# BX31_IoT_Board.net
KiCad netlist of a schematic drawn in EAGLE
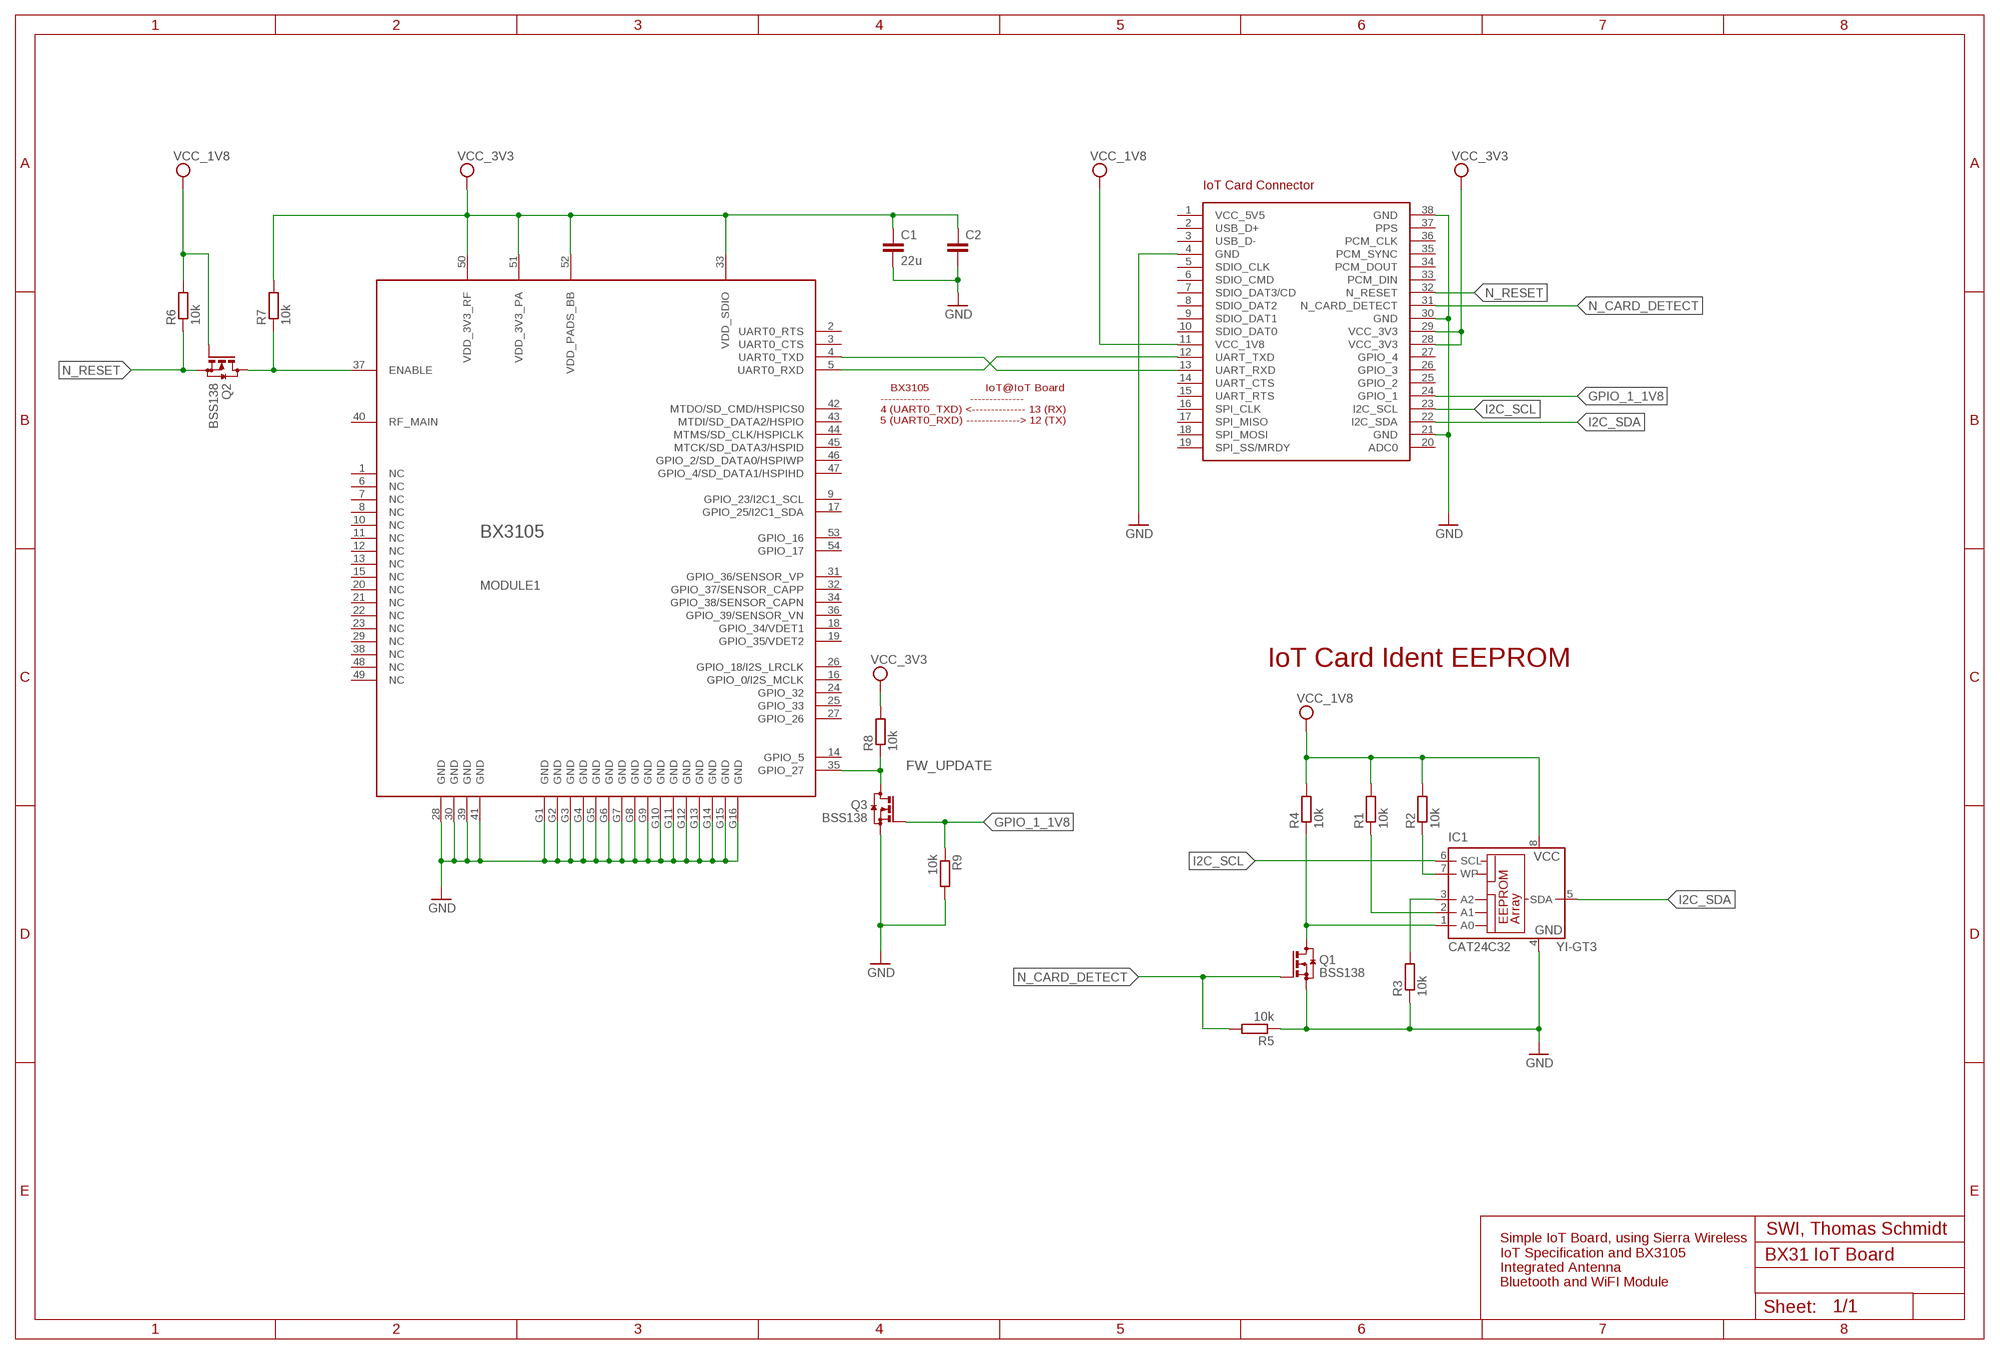
[diagram p0: schematic, sheet 1]

(export (version "E")
  (design (tool "Eeschema 10.0.6"))
  (components
    (comp (ref "C1")
      (value "22u")
      (footprint "eagle-import:C0805K")
      (libsource (lib "eagle-import") (part "C-EUC0805K"))
    )
    (comp (ref "C2")
      (value "C-EUC0603K")
      (footprint "eagle-import:C0603K")
      (libsource (lib "eagle-import") (part "C-EUC0603K"))
    )
    (comp (ref "IC1")
      (value "CAT24C32 YI-GT3")
      (footprint "eagle-import:TSSOP8")
      (fields (field (name "MPN") "CAT24C64YI-GT3"))
      (libsource (lib "eagle-import") (part "24STC64"))
    )
    (comp (ref "MODULE1")
      (value "BX3105")
      (footprint "eagle-import:BX3105")
      (libsource (lib "eagle-import") (part "BX3105"))
    )
    (comp (ref "Q1")
      (value "BSS138")
      (footprint "eagle-import:SOT23")
      (libsource (lib "eagle-import") (part "BSS123"))
    )
    (comp (ref "Q2")
      (value "BSS138")
      (footprint "eagle-import:SOT23")
      (libsource (lib "eagle-import") (part "BSS123"))
    )
    (comp (ref "Q3")
      (value "BSS138")
      (footprint "eagle-import:SOT23")
      (libsource (lib "eagle-import") (part "BSS123"))
    )
    (comp (ref "R1")
      (value "10k")
      (footprint "eagle-import:R0402")
      (libsource (lib "eagle-import") (part "R-EU_R0402"))
    )
    (comp (ref "R2")
      (value "10k")
      (footprint "eagle-import:R0402")
      (libsource (lib "eagle-import") (part "R-EU_R0402"))
    )
    (comp (ref "R3")
      (value "10k")
      (footprint "eagle-import:R0402")
      (libsource (lib "eagle-import") (part "R-EU_R0402"))
    )
    (comp (ref "R4")
      (value "10k")
      (footprint "eagle-import:R0402")
      (libsource (lib "eagle-import") (part "R-EU_R0402"))
    )
    (comp (ref "R5")
      (value "10k")
      (footprint "eagle-import:R0402")
      (libsource (lib "eagle-import") (part "R-EU_R0402"))
    )
    (comp (ref "R6")
      (value "10k")
      (footprint "eagle-import:R0402")
      (libsource (lib "eagle-import") (part "R-EU_R0402"))
    )
    (comp (ref "R7")
      (value "10k")
      (footprint "eagle-import:R0402")
      (libsource (lib "eagle-import") (part "R-EU_R0402"))
    )
    (comp (ref "R8")
      (value "10k")
      (footprint "eagle-import:R0402")
      (libsource (lib "eagle-import") (part "R-EU_R0402"))
    )
    (comp (ref "R9")
      (value "10k")
      (footprint "eagle-import:R0402")
      (libsource (lib "eagle-import") (part "R-EU_R0402"))
    )
    (comp (ref "U$1")
      (value "IOT")
      (footprint "eagle-import:IOT")
      (libsource (lib "eagle-import") (part "IOT"))
    )
  )
  (nets
    (net (code "1") (name "/FW_UPDATE") (class "Default")
      (node (ref "MODULE1") (pin "35") (pinfunction "GPIO_27_35") (pintype "bidirectional"))
      (node (ref "Q3") (pin "3") (pinfunction "D_3") (pintype "passive"))
      (node (ref "R8") (pin "1") (pinfunction "1_1") (pintype "passive"))
    )
    (net (code "2") (name "/VCC_5V5") (class "Default")
      (node (ref "U$1") (pin "1") (pinfunction "VCC_5V5_1") (pintype "power_in"))
    )
    (net (code "3") (name "GND") (class "Default")
      (node (ref "C1") (pin "2") (pinfunction "2_2") (pintype "passive"))
      (node (ref "C2") (pin "2") (pinfunction "2_2") (pintype "passive"))
      (node (ref "IC1") (pin "4") (pinfunction "GND_4") (pintype "power_in"))
      (node (ref "MODULE1") (pin "28") (pinfunction "GND_28") (pintype "power_in"))
      (node (ref "MODULE1") (pin "30") (pinfunction "GND_30") (pintype "power_in"))
      (node (ref "MODULE1") (pin "39") (pinfunction "GND_39") (pintype "power_in"))
      (node (ref "MODULE1") (pin "41") (pinfunction "GND_41") (pintype "power_in"))
      (node (ref "MODULE1") (pin "G1") (pinfunction "GND_G1") (pintype "power_in"))
      (node (ref "MODULE1") (pin "G10") (pinfunction "GND_G10") (pintype "power_in"))
      (node (ref "MODULE1") (pin "G11") (pinfunction "GND_G11") (pintype "power_in"))
      (node (ref "MODULE1") (pin "G12") (pinfunction "GND_G12") (pintype "power_in"))
      (node (ref "MODULE1") (pin "G13") (pinfunction "GND_G13") (pintype "power_in"))
      (node (ref "MODULE1") (pin "G14") (pinfunction "GND_G14") (pintype "power_in"))
      (node (ref "MODULE1") (pin "G15") (pinfunction "GND_G15") (pintype "power_in"))
      (node (ref "MODULE1") (pin "G16") (pinfunction "GND_G16") (pintype "power_in"))
      (node (ref "MODULE1") (pin "G2") (pinfunction "GND_G2") (pintype "power_in"))
      (node (ref "MODULE1") (pin "G3") (pinfunction "GND_G3") (pintype "power_in"))
      (node (ref "MODULE1") (pin "G4") (pinfunction "GND_G4") (pintype "power_in"))
      (node (ref "MODULE1") (pin "G5") (pinfunction "GND_G5") (pintype "power_in"))
      (node (ref "MODULE1") (pin "G6") (pinfunction "GND_G6") (pintype "power_in"))
      (node (ref "MODULE1") (pin "G7") (pinfunction "GND_G7") (pintype "power_in"))
      (node (ref "MODULE1") (pin "G8") (pinfunction "GND_G8") (pintype "power_in"))
      (node (ref "MODULE1") (pin "G9") (pinfunction "GND_G9") (pintype "power_in"))
      (node (ref "Q1") (pin "2") (pinfunction "S_2") (pintype "passive"))
      (node (ref "Q3") (pin "2") (pinfunction "S_2") (pintype "passive"))
      (node (ref "R3") (pin "1") (pinfunction "1_1") (pintype "passive"))
      (node (ref "R5") (pin "1") (pinfunction "1_1") (pintype "passive"))
      (node (ref "R9") (pin "2") (pinfunction "2_2") (pintype "passive"))
      (node (ref "U$1") (pin "21") (pinfunction "GND_21") (pintype "power_in"))
      (node (ref "U$1") (pin "30") (pinfunction "GND_30") (pintype "power_in"))
      (node (ref "U$1") (pin "38") (pinfunction "GND_38") (pintype "bidirectional"))
      (node (ref "U$1") (pin "4") (pinfunction "GND_4") (pintype "power_in"))
    )
    (net (code "4") (name "GPIO_1_1V8") (class "Default")
      (node (ref "Q3") (pin "1") (pinfunction "G_1") (pintype "passive"))
      (node (ref "R9") (pin "1") (pinfunction "1_1") (pintype "passive"))
      (node (ref "U$1") (pin "24") (pinfunction "GPIO_1_24") (pintype "bidirectional"))
    )
    (net (code "5") (name "I2C_SCL") (class "Default")
      (node (ref "IC1") (pin "6") (pinfunction "SCL_6") (pintype "input"))
      (node (ref "U$1") (pin "23") (pinfunction "I2C_SCL_23") (pintype "input"))
    )
    (net (code "6") (name "I2C_SDA") (class "Default")
      (node (ref "IC1") (pin "5") (pinfunction "SDA_5") (pintype "bidirectional"))
      (node (ref "U$1") (pin "22") (pinfunction "I2C_SDA_22") (pintype "bidirectional"))
    )
    (net (code "7") (name "N_CARD_DETECT") (class "Default")
      (node (ref "Q1") (pin "1") (pinfunction "G_1") (pintype "passive"))
      (node (ref "R5") (pin "2") (pinfunction "2_2") (pintype "passive"))
      (node (ref "U$1") (pin "31") (pinfunction "N_CARD_DETECT_31") (pintype "bidirectional"))
    )
    (net (code "8") (name "N_RESET") (class "Default")
      (node (ref "Q2") (pin "2") (pinfunction "S_2") (pintype "passive"))
      (node (ref "R6") (pin "1") (pinfunction "1_1") (pintype "passive"))
      (node (ref "U$1") (pin "32") (pinfunction "N_RESET_32") (pintype "bidirectional"))
    )
    (net (code "9") (name "Net-(IC1-A0)") (class "Default")
      (node (ref "IC1") (pin "1") (pinfunction "A0_1") (pintype "input"))
      (node (ref "Q1") (pin "3") (pinfunction "D_3") (pintype "passive"))
      (node (ref "R4") (pin "1") (pinfunction "1_1") (pintype "passive"))
    )
    (net (code "10") (name "Net-(IC1-A1)") (class "Default")
      (node (ref "IC1") (pin "2") (pinfunction "A1_2") (pintype "input"))
      (node (ref "R1") (pin "1") (pinfunction "1_1") (pintype "passive"))
    )
    (net (code "11") (name "Net-(IC1-A2)") (class "Default")
      (node (ref "IC1") (pin "3") (pinfunction "A2_3") (pintype "input"))
      (node (ref "R3") (pin "2") (pinfunction "2_2") (pintype "passive"))
    )
    (net (code "12") (name "Net-(IC1-WP)") (class "Default")
      (node (ref "IC1") (pin "7") (pinfunction "WP_7") (pintype "input"))
      (node (ref "R2") (pin "1") (pinfunction "1_1") (pintype "passive"))
    )
    (net (code "13") (name "Net-(MODULE1-ENABLE)") (class "Default")
      (node (ref "MODULE1") (pin "37") (pinfunction "ENABLE_37") (pintype "input"))
      (node (ref "Q2") (pin "3") (pinfunction "D_3") (pintype "passive"))
      (node (ref "R7") (pin "1") (pinfunction "1_1") (pintype "passive"))
    )
    (net (code "14") (name "Net-(MODULE1-UART0_RXD)") (class "Default")
      (node (ref "MODULE1") (pin "5") (pinfunction "UART0_RXD_5") (pintype "output"))
      (node (ref "U$1") (pin "12") (pinfunction "UART_TXD_12") (pintype "output"))
    )
    (net (code "15") (name "Net-(MODULE1-UART0_TXD)") (class "Default")
      (node (ref "MODULE1") (pin "4") (pinfunction "UART0_TXD_4") (pintype "input"))
      (node (ref "U$1") (pin "13") (pinfunction "UART_RXD_13") (pintype "input"))
    )
    (net (code "16") (name "VCC_1V8") (class "Default")
      (node (ref "IC1") (pin "8") (pinfunction "VCC_8") (pintype "power_in"))
      (node (ref "Q2") (pin "1") (pinfunction "G_1") (pintype "passive"))
      (node (ref "R1") (pin "2") (pinfunction "2_2") (pintype "passive"))
      (node (ref "R2") (pin "2") (pinfunction "2_2") (pintype "passive"))
      (node (ref "R4") (pin "2") (pinfunction "2_2") (pintype "passive"))
      (node (ref "R6") (pin "2") (pinfunction "2_2") (pintype "passive"))
      (node (ref "U$1") (pin "11") (pinfunction "VCC_1V8_11") (pintype "power_in"))
    )
    (net (code "17") (name "VCC_3V3") (class "Default")
      (node (ref "C1") (pin "1") (pinfunction "1_1") (pintype "passive"))
      (node (ref "C2") (pin "1") (pinfunction "1_1") (pintype "passive"))
      (node (ref "MODULE1") (pin "33") (pinfunction "VDD_SDIO_33") (pintype "power_in"))
      (node (ref "MODULE1") (pin "50") (pinfunction "VDD_3V3_RF_50") (pintype "power_in"))
      (node (ref "MODULE1") (pin "51") (pinfunction "VDD_3V3_PA_51") (pintype "power_in"))
      (node (ref "MODULE1") (pin "52") (pinfunction "VDD_PADS_BB_52") (pintype "power_in"))
      (node (ref "R7") (pin "2") (pinfunction "2_2") (pintype "passive"))
      (node (ref "R8") (pin "2") (pinfunction "2_2") (pintype "passive"))
      (node (ref "U$1") (pin "28") (pinfunction "VCC_3V3_28") (pintype "power_in"))
      (node (ref "U$1") (pin "29") (pinfunction "VCC_3V3_29") (pintype "power_in"))
    )
    (net (code "18") (name "unconnected-(MODULE1-GPIO_0{slash}I2S_MCLK-Pad16)") (class "Default")
      (node (ref "MODULE1") (pin "16") (pinfunction "GPIO_0/I2S_MCLK_16") (pintype "bidirectional"))
    )
    (net (code "19") (name "unconnected-(MODULE1-GPIO_2{slash}SD_DATA0{slash}HSPIWP-Pad46)") (class "Default")
      (node (ref "MODULE1") (pin "46") (pinfunction "GPIO_2/SD_DATA0/HSPIWP_46") (pintype "bidirectional"))
    )
    (net (code "20") (name "unconnected-(MODULE1-GPIO_4{slash}SD_DATA1{slash}HSPIHD-Pad47)") (class "Default")
      (node (ref "MODULE1") (pin "47") (pinfunction "GPIO_4/SD_DATA1/HSPIHD_47") (pintype "bidirectional"))
    )
    (net (code "21") (name "unconnected-(MODULE1-GPIO_5-Pad14)") (class "Default")
      (node (ref "MODULE1") (pin "14") (pinfunction "GPIO_5_14") (pintype "bidirectional"))
    )
    (net (code "22") (name "unconnected-(MODULE1-GPIO_16-Pad53)") (class "Default")
      (node (ref "MODULE1") (pin "53") (pinfunction "GPIO_16_53") (pintype "bidirectional"))
    )
    (net (code "23") (name "unconnected-(MODULE1-GPIO_17-Pad54)") (class "Default")
      (node (ref "MODULE1") (pin "54") (pinfunction "GPIO_17_54") (pintype "bidirectional"))
    )
    (net (code "24") (name "unconnected-(MODULE1-GPIO_18{slash}I2S_LRCLK-Pad26)") (class "Default")
      (node (ref "MODULE1") (pin "26") (pinfunction "GPIO_18/I2S_LRCLK_26") (pintype "bidirectional"))
    )
    (net (code "25") (name "unconnected-(MODULE1-GPIO_23{slash}I2C1_SCL-Pad9)") (class "Default")
      (node (ref "MODULE1") (pin "9") (pinfunction "GPIO_23/I2C1_SCL_9") (pintype "bidirectional"))
    )
    (net (code "26") (name "unconnected-(MODULE1-GPIO_25{slash}I2C1_SDA-Pad17)") (class "Default")
      (node (ref "MODULE1") (pin "17") (pinfunction "GPIO_25/I2C1_SDA_17") (pintype "bidirectional"))
    )
    (net (code "27") (name "unconnected-(MODULE1-GPIO_26-Pad27)") (class "Default")
      (node (ref "MODULE1") (pin "27") (pinfunction "GPIO_26_27") (pintype "bidirectional"))
    )
    (net (code "28") (name "unconnected-(MODULE1-GPIO_32-Pad24)") (class "Default")
      (node (ref "MODULE1") (pin "24") (pinfunction "GPIO_32_24") (pintype "bidirectional"))
    )
    (net (code "29") (name "unconnected-(MODULE1-GPIO_33-Pad25)") (class "Default")
      (node (ref "MODULE1") (pin "25") (pinfunction "GPIO_33_25") (pintype "bidirectional"))
    )
    (net (code "30") (name "unconnected-(MODULE1-GPIO_34{slash}VDET1-Pad18)") (class "Default")
      (node (ref "MODULE1") (pin "18") (pinfunction "GPIO_34/VDET1_18") (pintype "bidirectional"))
    )
    (net (code "31") (name "unconnected-(MODULE1-GPIO_35{slash}VDET2-Pad19)") (class "Default")
      (node (ref "MODULE1") (pin "19") (pinfunction "GPIO_35/VDET2_19") (pintype "bidirectional"))
    )
    (net (code "32") (name "unconnected-(MODULE1-GPIO_36{slash}SENSOR_VP-Pad31)") (class "Default")
      (node (ref "MODULE1") (pin "31") (pinfunction "GPIO_36/SENSOR_VP_31") (pintype "bidirectional"))
    )
    (net (code "33") (name "unconnected-(MODULE1-GPIO_37{slash}SENSOR_CAPP-Pad32)") (class "Default")
      (node (ref "MODULE1") (pin "32") (pinfunction "GPIO_37/SENSOR_CAPP_32") (pintype "bidirectional"))
    )
    (net (code "34") (name "unconnected-(MODULE1-GPIO_38{slash}SENSOR_CAPN-Pad34)") (class "Default")
      (node (ref "MODULE1") (pin "34") (pinfunction "GPIO_38/SENSOR_CAPN_34") (pintype "bidirectional"))
    )
    (net (code "35") (name "unconnected-(MODULE1-GPIO_39{slash}SENSOR_VN-Pad36)") (class "Default")
      (node (ref "MODULE1") (pin "36") (pinfunction "GPIO_39/SENSOR_VN_36") (pintype "bidirectional"))
    )
    (net (code "36") (name "unconnected-(MODULE1-MTCK{slash}SD_DATA3{slash}HSPID-Pad45)") (class "Default")
      (node (ref "MODULE1") (pin "45") (pinfunction "MTCK/SD_DATA3/HSPID_45") (pintype "bidirectional"))
    )
    (net (code "37") (name "unconnected-(MODULE1-MTDI{slash}SD_DATA2{slash}HSPIO-Pad43)") (class "Default")
      (node (ref "MODULE1") (pin "43") (pinfunction "MTDI/SD_DATA2/HSPIO_43") (pintype "bidirectional"))
    )
    (net (code "38") (name "unconnected-(MODULE1-MTDO{slash}SD_CMD{slash}HSPICS0-Pad42)") (class "Default")
      (node (ref "MODULE1") (pin "42") (pinfunction "MTDO/SD_CMD/HSPICS0_42") (pintype "bidirectional"))
    )
    (net (code "39") (name "unconnected-(MODULE1-MTMS{slash}SD_CLK{slash}HSPICLK-Pad44)") (class "Default")
      (node (ref "MODULE1") (pin "44") (pinfunction "MTMS/SD_CLK/HSPICLK_44") (pintype "bidirectional"))
    )
    (net (code "40") (name "unconnected-(MODULE1-NC-Pad1)") (class "Default")
      (node (ref "MODULE1") (pin "1") (pinfunction "NC_1") (pintype "no_connect"))
    )
    (net (code "41") (name "unconnected-(MODULE1-NC-Pad6)") (class "Default")
      (node (ref "MODULE1") (pin "6") (pinfunction "NC_6") (pintype "no_connect"))
    )
    (net (code "42") (name "unconnected-(MODULE1-NC-Pad7)") (class "Default")
      (node (ref "MODULE1") (pin "7") (pinfunction "NC_7") (pintype "no_connect"))
    )
    (net (code "43") (name "unconnected-(MODULE1-NC-Pad8)") (class "Default")
      (node (ref "MODULE1") (pin "8") (pinfunction "NC_8") (pintype "no_connect"))
    )
    (net (code "44") (name "unconnected-(MODULE1-NC-Pad10)") (class "Default")
      (node (ref "MODULE1") (pin "10") (pinfunction "NC_10") (pintype "no_connect"))
    )
    (net (code "45") (name "unconnected-(MODULE1-NC-Pad11)") (class "Default")
      (node (ref "MODULE1") (pin "11") (pinfunction "NC_11") (pintype "no_connect"))
    )
    (net (code "46") (name "unconnected-(MODULE1-NC-Pad12)") (class "Default")
      (node (ref "MODULE1") (pin "12") (pinfunction "NC_12") (pintype "no_connect"))
    )
    (net (code "47") (name "unconnected-(MODULE1-NC-Pad13)") (class "Default")
      (node (ref "MODULE1") (pin "13") (pinfunction "NC_13") (pintype "no_connect"))
    )
    (net (code "48") (name "unconnected-(MODULE1-NC-Pad15)") (class "Default")
      (node (ref "MODULE1") (pin "15") (pinfunction "NC_15") (pintype "no_connect"))
    )
    (net (code "49") (name "unconnected-(MODULE1-NC-Pad20)") (class "Default")
      (node (ref "MODULE1") (pin "20") (pinfunction "NC_20") (pintype "no_connect"))
    )
    (net (code "50") (name "unconnected-(MODULE1-NC-Pad21)") (class "Default")
      (node (ref "MODULE1") (pin "21") (pinfunction "NC_21") (pintype "no_connect"))
    )
    (net (code "51") (name "unconnected-(MODULE1-NC-Pad22)") (class "Default")
      (node (ref "MODULE1") (pin "22") (pinfunction "NC_22") (pintype "no_connect"))
    )
    (net (code "52") (name "unconnected-(MODULE1-NC-Pad23)") (class "Default")
      (node (ref "MODULE1") (pin "23") (pinfunction "NC_23") (pintype "no_connect"))
    )
    (net (code "53") (name "unconnected-(MODULE1-NC-Pad29)") (class "Default")
      (node (ref "MODULE1") (pin "29") (pinfunction "NC_29") (pintype "no_connect"))
    )
    (net (code "54") (name "unconnected-(MODULE1-NC-Pad38)") (class "Default")
      (node (ref "MODULE1") (pin "38") (pinfunction "NC_38") (pintype "no_connect"))
    )
    (net (code "55") (name "unconnected-(MODULE1-NC-Pad48)") (class "Default")
      (node (ref "MODULE1") (pin "48") (pinfunction "NC_48") (pintype "no_connect"))
    )
    (net (code "56") (name "unconnected-(MODULE1-NC-Pad49)") (class "Default")
      (node (ref "MODULE1") (pin "49") (pinfunction "NC_49") (pintype "no_connect"))
    )
    (net (code "57") (name "unconnected-(MODULE1-RF_MAIN-Pad40)") (class "Default")
      (node (ref "MODULE1") (pin "40") (pinfunction "RF_MAIN_40") (pintype "bidirectional"))
    )
    (net (code "58") (name "unconnected-(MODULE1-UART0_CTS-Pad3)") (class "Default")
      (node (ref "MODULE1") (pin "3") (pinfunction "UART0_CTS_3") (pintype "output"))
    )
    (net (code "59") (name "unconnected-(MODULE1-UART0_RTS-Pad2)") (class "Default")
      (node (ref "MODULE1") (pin "2") (pinfunction "UART0_RTS_2") (pintype "input"))
    )
    (net (code "60") (name "unconnected-(U$1-ADC0-Pad20)") (class "Default")
      (node (ref "U$1") (pin "20") (pinfunction "ADC0_20") (pintype "output"))
    )
    (net (code "61") (name "unconnected-(U$1-GPIO_2-Pad25)") (class "Default")
      (node (ref "U$1") (pin "25") (pinfunction "GPIO_2_25") (pintype "bidirectional"))
    )
    (net (code "62") (name "unconnected-(U$1-GPIO_3-Pad26)") (class "Default")
      (node (ref "U$1") (pin "26") (pinfunction "GPIO_3_26") (pintype "bidirectional"))
    )
    (net (code "63") (name "unconnected-(U$1-GPIO_4-Pad27)") (class "Default")
      (node (ref "U$1") (pin "27") (pinfunction "GPIO_4_27") (pintype "bidirectional"))
    )
    (net (code "64") (name "unconnected-(U$1-PCM_CLK-Pad36)") (class "Default")
      (node (ref "U$1") (pin "36") (pinfunction "PCM_CLK_36") (pintype "input"))
    )
    (net (code "65") (name "unconnected-(U$1-PCM_DIN-Pad33)") (class "Default")
      (node (ref "U$1") (pin "33") (pinfunction "PCM_DIN_33") (pintype "output"))
    )
    (net (code "66") (name "unconnected-(U$1-PCM_DOUT-Pad34)") (class "Default")
      (node (ref "U$1") (pin "34") (pinfunction "PCM_DOUT_34") (pintype "input"))
    )
    (net (code "67") (name "unconnected-(U$1-PCM_SYNC-Pad35)") (class "Default")
      (node (ref "U$1") (pin "35") (pinfunction "PCM_SYNC_35") (pintype "input"))
    )
    (net (code "68") (name "unconnected-(U$1-PPS-Pad37)") (class "Default")
      (node (ref "U$1") (pin "37") (pinfunction "PPS_37") (pintype "input"))
    )
    (net (code "69") (name "unconnected-(U$1-SDIO_CLK-Pad5)") (class "Default")
      (node (ref "U$1") (pin "5") (pinfunction "SDIO_CLK_5") (pintype "input"))
    )
    (net (code "70") (name "unconnected-(U$1-SDIO_CMD-Pad6)") (class "Default")
      (node (ref "U$1") (pin "6") (pinfunction "SDIO_CMD_6") (pintype "input"))
    )
    (net (code "71") (name "unconnected-(U$1-SDIO_DAT0-Pad10)") (class "Default")
      (node (ref "U$1") (pin "10") (pinfunction "SDIO_DAT0_10") (pintype "bidirectional"))
    )
    (net (code "72") (name "unconnected-(U$1-SDIO_DAT1-Pad9)") (class "Default")
      (node (ref "U$1") (pin "9") (pinfunction "SDIO_DAT1_9") (pintype "bidirectional"))
    )
    (net (code "73") (name "unconnected-(U$1-SDIO_DAT2-Pad8)") (class "Default")
      (node (ref "U$1") (pin "8") (pinfunction "SDIO_DAT2_8") (pintype "bidirectional"))
    )
    (net (code "74") (name "unconnected-(U$1-SDIO_DAT3{slash}CD-Pad7)") (class "Default")
      (node (ref "U$1") (pin "7") (pinfunction "SDIO_DAT3/CD_7") (pintype "bidirectional"))
    )
    (net (code "75") (name "unconnected-(U$1-SPI_CLK-Pad16)") (class "Default")
      (node (ref "U$1") (pin "16") (pinfunction "SPI_CLK_16") (pintype "input"))
    )
    (net (code "76") (name "unconnected-(U$1-SPI_MISO-Pad17)") (class "Default")
      (node (ref "U$1") (pin "17") (pinfunction "SPI_MISO_17") (pintype "output"))
    )
    (net (code "77") (name "unconnected-(U$1-SPI_MOSI-Pad18)") (class "Default")
      (node (ref "U$1") (pin "18") (pinfunction "SPI_MOSI_18") (pintype "input"))
    )
    (net (code "78") (name "unconnected-(U$1-SPI_SS{slash}MRDY-Pad19)") (class "Default")
      (node (ref "U$1") (pin "19") (pinfunction "SPI_SS/MRDY_19") (pintype "input"))
    )
    (net (code "79") (name "unconnected-(U$1-UART_CTS-Pad14)") (class "Default")
      (node (ref "U$1") (pin "14") (pinfunction "UART_CTS_14") (pintype "input"))
    )
    (net (code "80") (name "unconnected-(U$1-UART_RTS-Pad15)") (class "Default")
      (node (ref "U$1") (pin "15") (pinfunction "UART_RTS_15") (pintype "output"))
    )
    (net (code "81") (name "unconnected-(U$1-USB_D+-Pad2)") (class "Default")
      (node (ref "U$1") (pin "2") (pinfunction "USB_D+_2") (pintype "bidirectional"))
    )
    (net (code "82") (name "unconnected-(U$1-USB_D--Pad3)") (class "Default")
      (node (ref "U$1") (pin "3") (pinfunction "USB_D-_3") (pintype "bidirectional"))
    )
  )
)
